# SparkFun_Motor_Driver-TB6612FNG_v11c.net
KiCad netlist of a schematic drawn in Altium Designer
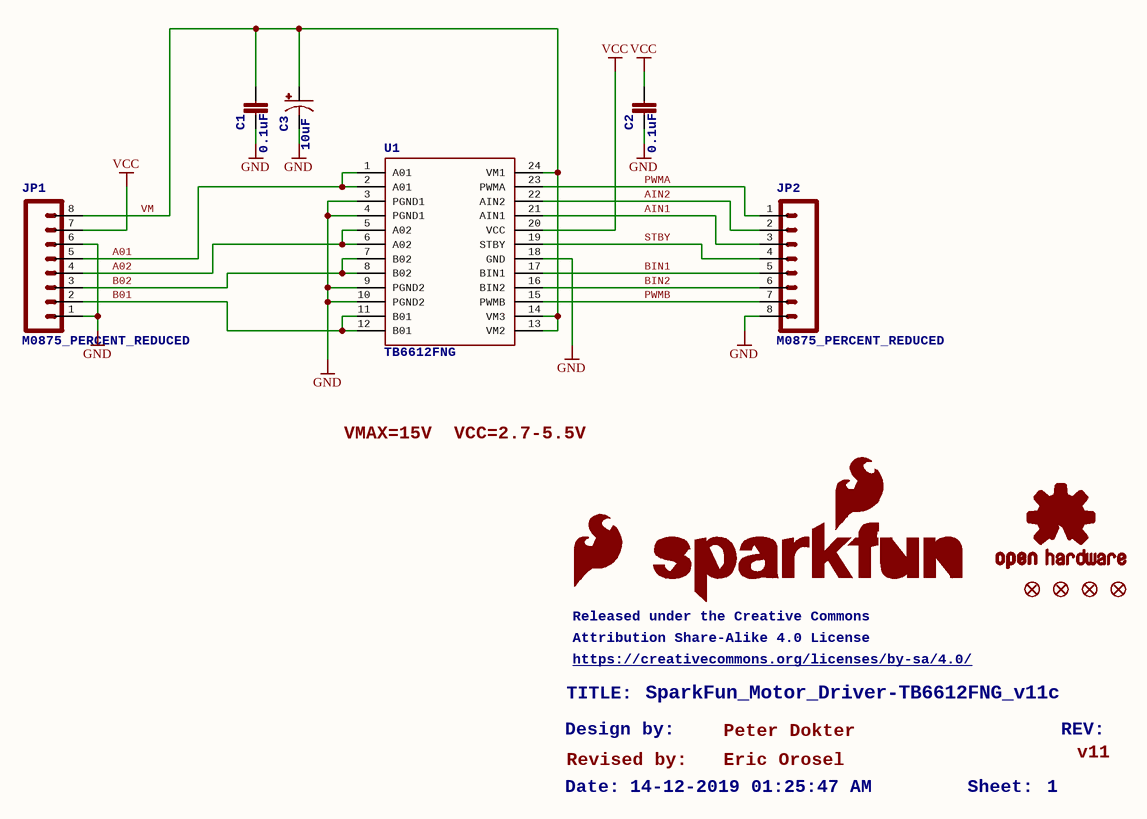
[diagram p0: SparkFun_Motor_Driver-TB6612FNG_v11c.SchDoc]

(export (version "E")
  (design (tool "Eeschema 10.0.6"))
  (components
    (comp (ref "C1")
      (value "0.1uF")
      (footprint "0402")
      (libsource (lib "SparkFun-Capacitors") (part "0.1UF-0402-16V-10%"))
    )
    (comp (ref "C2")
      (value "0.1uF")
      (footprint "0402")
      (libsource (lib "SparkFun-Capacitors") (part "0.1UF-0402-16V-10%"))
    )
    (comp (ref "C3")
      (value "10uF")
      (footprint "EIA3528")
      (libsource (lib "SparkFun-Capacitors") (part "10UF-POLAR-EIA3528-20V-10%(TANT)"))
    )
    (comp (ref "FD1")
      (value "FIDUCIALUFIDUCIAL")
      (footprint "FIDUCIAL-MICRO")
      (libsource (lib "SparkFun-Aesthetics") (part "FIDUCIALUFIDUCIAL"))
    )
    (comp (ref "FD2")
      (value "FIDUCIALUFIDUCIAL")
      (footprint "FIDUCIAL-MICRO")
      (libsource (lib "SparkFun-Aesthetics") (part "FIDUCIALUFIDUCIAL"))
    )
    (comp (ref "FD3")
      (value "FIDUCIALUFIDUCIAL")
      (footprint "FIDUCIAL-MICRO")
      (libsource (lib "SparkFun-Aesthetics") (part "FIDUCIALUFIDUCIAL"))
    )
    (comp (ref "FD4")
      (value "FIDUCIALUFIDUCIAL")
      (footprint "FIDUCIAL-MICRO")
      (libsource (lib "SparkFun-Aesthetics") (part "FIDUCIALUFIDUCIAL"))
    )
    (comp (ref "JP1")
      (value "M0875_PERCENT_REDUCED")
      (footprint "1X08_OFFSET_REDUCED")
      (libsource (lib "Testing") (part "M0875_PERCENT_REDUCED"))
    )
    (comp (ref "JP2")
      (value "M0875_PERCENT_REDUCED")
      (footprint "1X08_OFFSET_REDUCED")
      (libsource (lib "Testing") (part "M0875_PERCENT_REDUCED"))
    )
    (comp (ref "LOGO1")
      (value "SFE_LOGO_FLAME.1_INCH")
      (footprint "SFE_LOGO_FLAME_.1")
      (libsource (lib "SparkFun-Aesthetics") (part "SFE_LOGO_FLAME.1_INCH"))
    )
    (comp (ref "LOGO2")
      (value "OSHW-LOGOS")
      (footprint "OSHW-LOGO-S")
      (libsource (lib "SparkFun-Aesthetics") (part "OSHW-LOGOS"))
    )
    (comp (ref "LOGO4")
      (value "SFE_LOGO_NAME_FLAME.1_INCH")
      (footprint "SFE_LOGO_NAME_FLAME_.1")
      (libsource (lib "SparkFun-Aesthetics") (part "SFE_LOGO_NAME_FLAME.1_INCH"))
    )
    (comp (ref "U1")
      (value "TB6612FNG")
      (footprint "SSOP24")
      (description "Toshiba 1A dual motor driver IC-09363")
      (libsource (lib "SparkFun-IC-Special-Function") (part "TB6612FNG"))
    )
  )
  (nets
    (net (code "1") (name "/A01") (class "Default")
      (node (ref "JP1") (pin "5") (pinfunction "5_5") (pintype "passive"))
      (node (ref "U1") (pin "1") (pinfunction "A01_1") (pintype "passive"))
      (node (ref "U1") (pin "2") (pinfunction "A01_2") (pintype "passive"))
    )
    (net (code "2") (name "/A02") (class "Default")
      (node (ref "JP1") (pin "4") (pinfunction "4_4") (pintype "passive"))
      (node (ref "U1") (pin "5") (pinfunction "A02_5") (pintype "passive"))
      (node (ref "U1") (pin "6") (pinfunction "A02_6") (pintype "passive"))
    )
    (net (code "3") (name "/AIN1") (class "Default")
      (node (ref "JP2") (pin "3") (pinfunction "3_3") (pintype "passive"))
      (node (ref "U1") (pin "21") (pinfunction "AIN1_21") (pintype "passive"))
    )
    (net (code "4") (name "/AIN2") (class "Default")
      (node (ref "JP2") (pin "2") (pinfunction "2_2") (pintype "passive"))
      (node (ref "U1") (pin "22") (pinfunction "AIN2_22") (pintype "passive"))
    )
    (net (code "5") (name "/B01") (class "Default")
      (node (ref "JP1") (pin "2") (pinfunction "2_2") (pintype "passive"))
      (node (ref "U1") (pin "11") (pinfunction "B01_11") (pintype "passive"))
      (node (ref "U1") (pin "12") (pinfunction "B01_12") (pintype "passive"))
    )
    (net (code "6") (name "/B02") (class "Default")
      (node (ref "JP1") (pin "3") (pinfunction "3_3") (pintype "passive"))
      (node (ref "U1") (pin "7") (pinfunction "B02_7") (pintype "passive"))
      (node (ref "U1") (pin "8") (pinfunction "B02_8") (pintype "passive"))
    )
    (net (code "7") (name "/BIN1") (class "Default")
      (node (ref "JP2") (pin "5") (pinfunction "5_5") (pintype "passive"))
      (node (ref "U1") (pin "17") (pinfunction "BIN1_17") (pintype "passive"))
    )
    (net (code "8") (name "/BIN2") (class "Default")
      (node (ref "JP2") (pin "6") (pinfunction "6_6") (pintype "passive"))
      (node (ref "U1") (pin "16") (pinfunction "BIN2_16") (pintype "passive"))
    )
    (net (code "9") (name "/PWMA") (class "Default")
      (node (ref "JP2") (pin "1") (pinfunction "1_1") (pintype "passive"))
      (node (ref "U1") (pin "23") (pinfunction "PWMA_23") (pintype "passive"))
    )
    (net (code "10") (name "/PWMB") (class "Default")
      (node (ref "JP2") (pin "7") (pinfunction "7_7") (pintype "passive"))
      (node (ref "U1") (pin "15") (pinfunction "PWMB_15") (pintype "passive"))
    )
    (net (code "11") (name "/STBY") (class "Default")
      (node (ref "JP2") (pin "4") (pinfunction "4_4") (pintype "passive"))
      (node (ref "U1") (pin "19") (pinfunction "STBY_19") (pintype "passive"))
    )
    (net (code "12") (name "/VM") (class "Default")
      (node (ref "C1") (pin "1") (pinfunction "1_1") (pintype "passive"))
      (node (ref "C3") (pin "A") (pinfunction "+_A") (pintype "passive"))
      (node (ref "JP1") (pin "8") (pinfunction "8_8") (pintype "passive"))
      (node (ref "U1") (pin "13") (pinfunction "VM2_13") (pintype "passive"))
      (node (ref "U1") (pin "14") (pinfunction "VM3_14") (pintype "passive"))
      (node (ref "U1") (pin "24") (pinfunction "VM1_24") (pintype "passive"))
    )
    (net (code "13") (name "GND") (class "Default")
      (node (ref "C1") (pin "2") (pinfunction "2_2") (pintype "passive"))
      (node (ref "C2") (pin "2") (pinfunction "2_2") (pintype "passive"))
      (node (ref "C3") (pin "C") (pinfunction "-_C") (pintype "passive"))
      (node (ref "JP1") (pin "1") (pinfunction "1_1") (pintype "passive"))
      (node (ref "JP1") (pin "6") (pinfunction "6_6") (pintype "passive"))
      (node (ref "JP2") (pin "8") (pinfunction "8_8") (pintype "passive"))
      (node (ref "U1") (pin "10") (pinfunction "PGND2_10") (pintype "passive"))
      (node (ref "U1") (pin "18") (pinfunction "GND_18") (pintype "passive"))
      (node (ref "U1") (pin "3") (pinfunction "PGND1_3") (pintype "passive"))
      (node (ref "U1") (pin "4") (pinfunction "PGND1_4") (pintype "passive"))
      (node (ref "U1") (pin "9") (pinfunction "PGND2_9") (pintype "passive"))
    )
    (net (code "14") (name "VCC") (class "Default")
      (node (ref "C2") (pin "1") (pinfunction "1_1") (pintype "passive"))
      (node (ref "JP1") (pin "7") (pinfunction "7_7") (pintype "passive"))
      (node (ref "U1") (pin "20") (pinfunction "VCC_20") (pintype "passive"))
    )
  )
)
